# airswimmer-controller.net
KiCad netlist of a schematic drawn in EAGLE
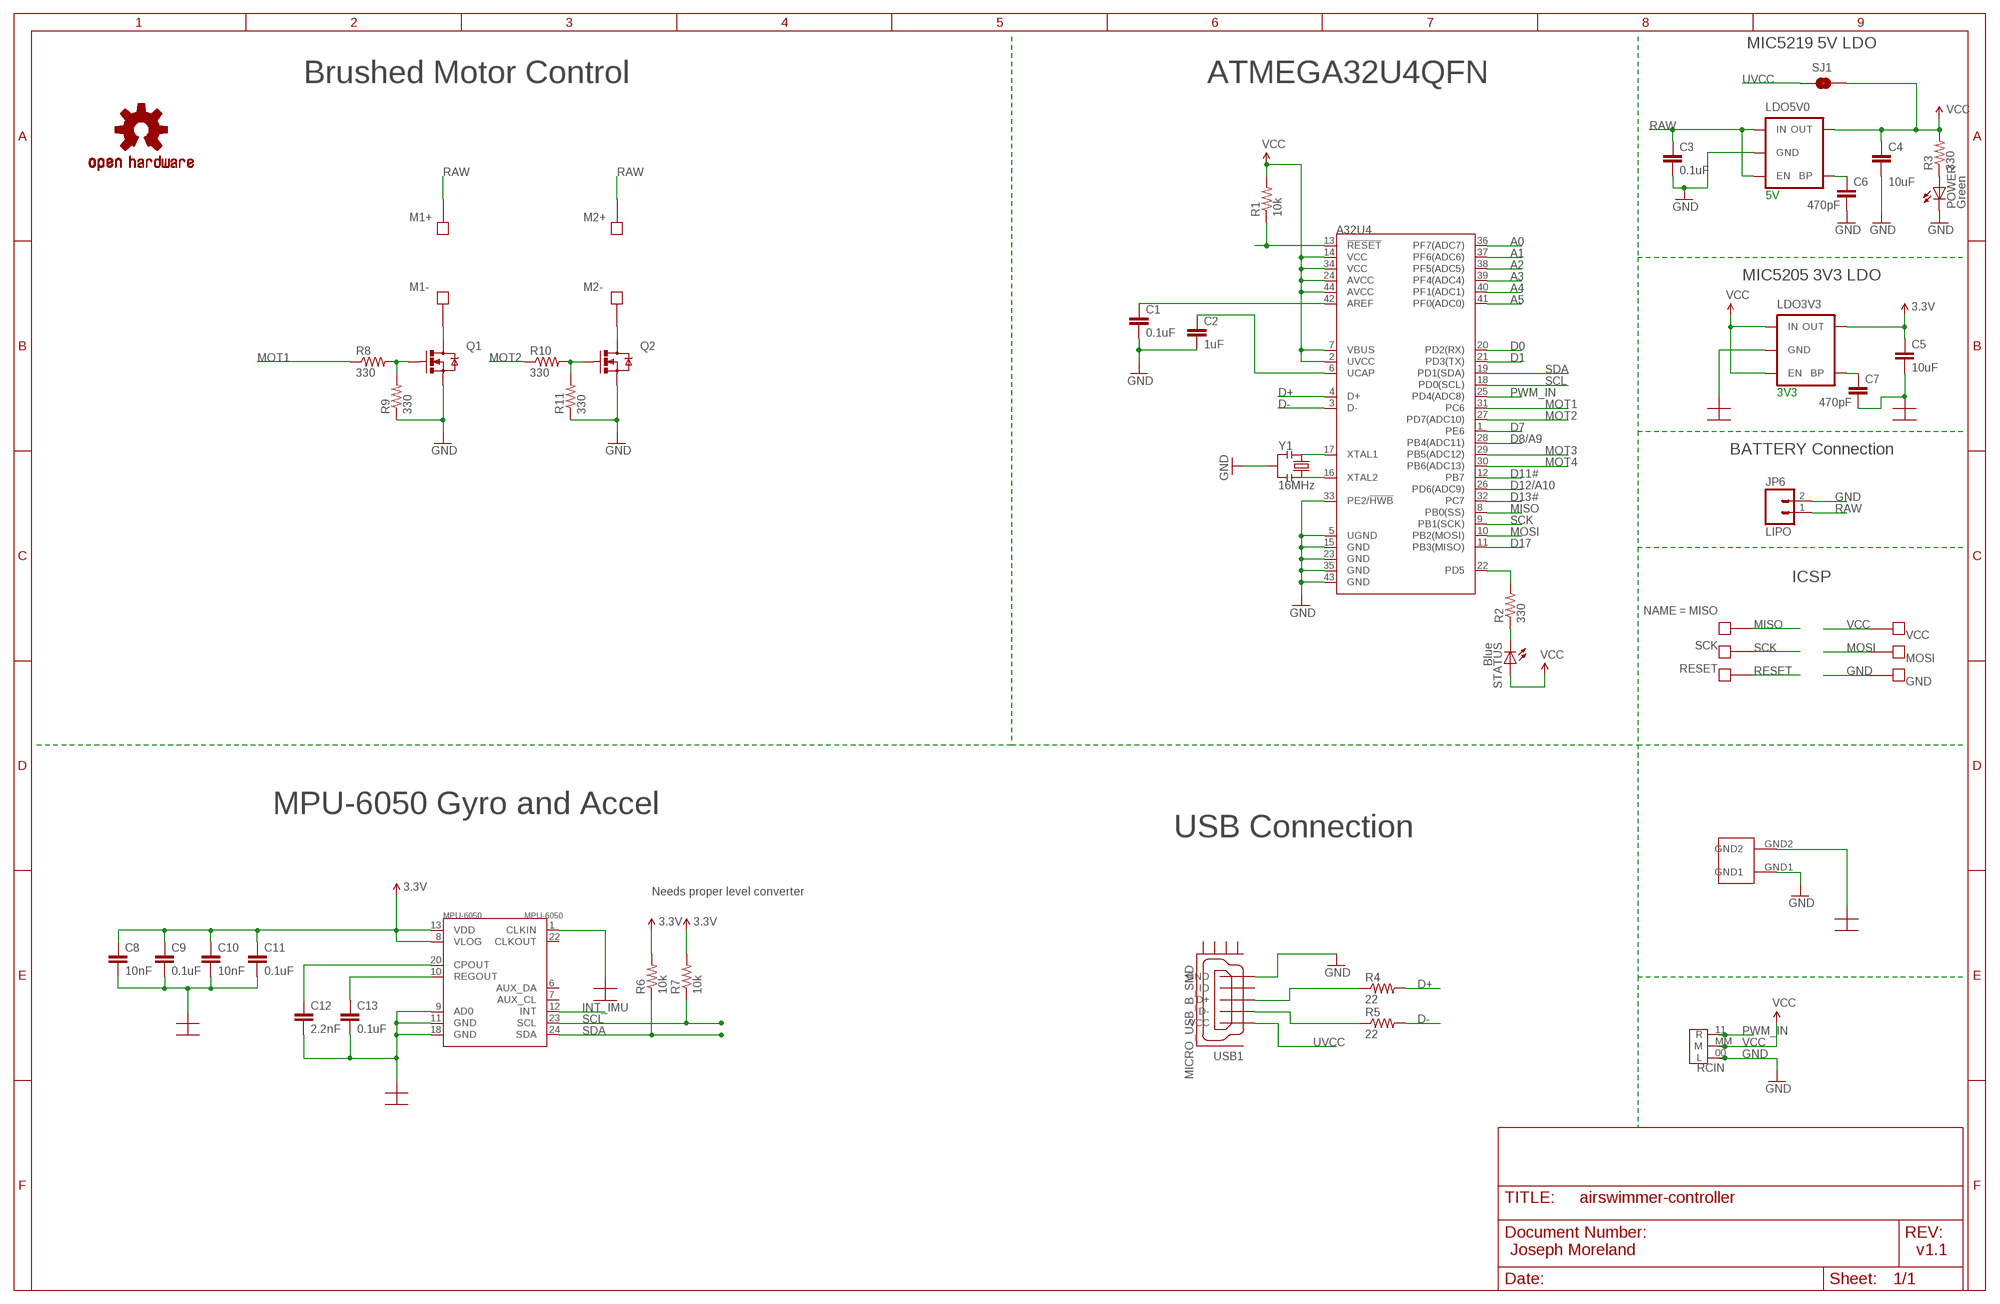
[diagram p0: schematic, sheet 1]

(export (version "E")
  (design (tool "Eeschema 10.0.6"))
  (components
    (comp (ref "A32U4")
      (value "ATMEGA32U4QFN")
      (footprint "eagle-import:ATMEL_QFN-44_SMALL_PAD")
      (fields (field (name "PARTNO") "ATMEGA32U4-MU"))
      (libsource (lib "eagle-import") (part "ATMEGA32U4QFN"))
    )
    (comp (ref "C1")
      (value "0.1uF")
      (footprint "eagle-import:SPARKFUN_0402-CAP")
      (fields (field (name "PARTNO") "GMK105BJ104KV-F"))
      (libsource (lib "eagle-import") (part "SPARKFUN_CAP0402-CAP"))
    )
    (comp (ref "C2")
      (value "1uF")
      (footprint "eagle-import:SPARKFUN_0402-CAP")
      (fields (field (name "PARTNO") "LMK105BJ105KV-F"))
      (libsource (lib "eagle-import") (part "SPARKFUN_CAP0402-CAP"))
    )
    (comp (ref "C3")
      (value "0.1uF")
      (footprint "eagle-import:SPARKFUN_0402-CAP")
      (fields (field (name "PARTNO") "GMK105BJ104KV-F"))
      (libsource (lib "eagle-import") (part "SPARKFUN_CAP0402-CAP"))
    )
    (comp (ref "C4")
      (value "10uF")
      (footprint "eagle-import:0603-CAP")
      (fields (field (name "PARTNO") "TCM1A106M8R"))
      (libsource (lib "eagle-import") (part "CAP0603-CAP"))
    )
    (comp (ref "C5")
      (value "10uF")
      (footprint "eagle-import:0603-CAP")
      (fields (field (name "PARTNO") "TCM1A106M8R"))
      (libsource (lib "eagle-import") (part "CAP0603-CAP"))
    )
    (comp (ref "C6")
      (value "470pF")
      (footprint "eagle-import:0603-CAP")
      (fields (field (name "PARTNO") "C0603C471K5RACTU"))
      (libsource (lib "eagle-import") (part "CAP0603-CAP"))
    )
    (comp (ref "C7")
      (value "470pF")
      (footprint "eagle-import:0603-CAP")
      (fields (field (name "PARTNO") "C0603C471K5RACTU"))
      (libsource (lib "eagle-import") (part "CAP0603-CAP"))
    )
    (comp (ref "C8")
      (value "10nF")
      (footprint "eagle-import:0402-CAP")
      (fields (field (name "PARTNO") "C0402C103K8RACTU"))
      (libsource (lib "eagle-import") (part "CAP0402-CAP"))
    )
    (comp (ref "C9")
      (value "0.1uF")
      (footprint "eagle-import:0402-CAP")
      (fields (field (name "PARTNO") "GMK105BJ104KV-F"))
      (libsource (lib "eagle-import") (part "CAP0402-CAP"))
    )
    (comp (ref "C10")
      (value "10nF")
      (footprint "eagle-import:0402-CAP")
      (fields (field (name "PARTNO") "C0402C103K8RACTU"))
      (libsource (lib "eagle-import") (part "CAP0402-CAP"))
    )
    (comp (ref "C11")
      (value "0.1uF")
      (footprint "eagle-import:0402-CAP")
      (fields (field (name "PARTNO") "GMK105BJ104KV-F"))
      (libsource (lib "eagle-import") (part "CAP0402-CAP"))
    )
    (comp (ref "C12")
      (value "2.2nF")
      (footprint "eagle-import:0402-CAP")
      (fields (field (name "PARTNO") "C0402C222K4RACTU"))
      (libsource (lib "eagle-import") (part "CAP0402-CAP"))
    )
    (comp (ref "C13")
      (value "0.1uF")
      (footprint "eagle-import:0402-CAP")
      (fields (field (name "PARTNO") "GMK105BJ104KV-F"))
      (libsource (lib "eagle-import") (part "CAP0402-CAP"))
    )
    (comp (ref "GND")
      (value "TEST_PAD")
      (footprint "eagle-import:ICSP_PAD")
      (fields (field (name "PARTNO") "DNP"))
      (libsource (lib "eagle-import") (part "TEST_PAD"))
    )
    (comp (ref "GND_SHORT")
      (value "GND_SHORT")
      (footprint "eagle-import:GND_SHORT")
      (fields (field (name "PARTNO") "DNP"))
      (libsource (lib "eagle-import") (part "GND_SHORT"))
    )
    (comp (ref "JP6")
      (value "LIPO")
      (footprint "eagle-import:1X02_LOCK")
      (fields (field (name "PARTNO") "DNP"))
      (libsource (lib "eagle-import") (part "M02LOCK"))
    )
    (comp (ref "LDO3V3")
      (value "V_REG_MIC52193.3V")
      (footprint "eagle-import:SOT23-5")
      (fields (field (name "PARTNO") "MIC5219-3.3YM5 TR"))
      (libsource (lib "eagle-import") (part "V_REG_MIC52193.3V"))
    )
    (comp (ref "LDO5V0")
      (value "MIC5219")
      (footprint "eagle-import:SOT23-5")
      (fields (field (name "PARTNO") "MIC5219-5.0YM5 TR"))
      (libsource (lib "eagle-import") (part "V_REG_MIC52195V"))
    )
    (comp (ref "LOGO1")
      (value "OSHW-LOGOM")
      (footprint "eagle-import:OSHW-LOGO-M")
      (fields (field (name "PARTNO") "DNP"))
      (libsource (lib "eagle-import") (part "OSHW-LOGOM"))
    )
    (comp (ref "M1+")
      (value "SOLDER_PAD.05X.05")
      (footprint "eagle-import:SOLDER_PAD_.05X.05")
      (fields (field (name "PARTNO") "DNP"))
      (libsource (lib "eagle-import") (part "SOLDER_PAD.05X.05"))
    )
    (comp (ref "M1-")
      (value "SOLDER_PAD.05X.05")
      (footprint "eagle-import:SOLDER_PAD_.05X.05")
      (fields (field (name "PARTNO") "DNP"))
      (libsource (lib "eagle-import") (part "SOLDER_PAD.05X.05"))
    )
    (comp (ref "M2+")
      (value "SOLDER_PAD.05X.05")
      (footprint "eagle-import:SOLDER_PAD_.05X.05")
      (fields (field (name "PARTNO") "DNP"))
      (libsource (lib "eagle-import") (part "SOLDER_PAD.05X.05"))
    )
    (comp (ref "M2-")
      (value "SOLDER_PAD.05X.05")
      (footprint "eagle-import:SOLDER_PAD_.05X.05")
      (fields (field (name "PARTNO") "DNP"))
      (libsource (lib "eagle-import") (part "SOLDER_PAD.05X.05"))
    )
    (comp (ref "MISO")
      (value "TEST_PAD")
      (footprint "eagle-import:ICSP_PAD")
      (fields (field (name "PARTNO") "DNP"))
      (libsource (lib "eagle-import") (part "TEST_PAD"))
    )
    (comp (ref "MOSI")
      (value "TEST_PAD")
      (footprint "eagle-import:ICSP_PAD")
      (fields (field (name "PARTNO") "DNP"))
      (libsource (lib "eagle-import") (part "TEST_PAD"))
    )
    (comp (ref "MPU-6050")
      (value "MPU-6050")
      (footprint "eagle-import:QFN-24")
      (libsource (lib "eagle-import") (part "IMU3000"))
    )
    (comp (ref "POWER")
      (value "Green")
      (footprint "eagle-import:LED-0603")
      (fields (field (name "PARTNO") "LTST-C190KGKT"))
      (libsource (lib "eagle-import") (part "LED0603"))
    )
    (comp (ref "Q1")
      (value "MOSFET-NCHANNELBSS123LT1G")
      (footprint "eagle-import:SOT23")
      (fields (field (name "PARTNO") "DMG6968U-7"))
      (libsource (lib "eagle-import") (part "MOSFET-NCHANNELBSS123LT1G"))
    )
    (comp (ref "Q2")
      (value "MOSFET-NCHANNELBSS123LT1G")
      (footprint "eagle-import:SOT23")
      (fields (field (name "PARTNO") "DMG6968U-7"))
      (libsource (lib "eagle-import") (part "MOSFET-NCHANNELBSS123LT1G"))
    )
    (comp (ref "R1")
      (value "10k")
      (footprint "eagle-import:0402-RES")
      (fields (field (name "PARTNO") "CRCW040210K0FKED"))
      (libsource (lib "eagle-import") (part "SparkFun-Resistors_RESISTOR0402-RES"))
    )
    (comp (ref "R2")
      (value "330")
      (footprint "eagle-import:0402-RES")
      (fields (field (name "PARTNO") "CRCW0402330RJNED"))
      (libsource (lib "eagle-import") (part "SparkFun-Resistors_RESISTOR0402-RES"))
    )
    (comp (ref "R3")
      (value "330")
      (footprint "eagle-import:0402-RES")
      (fields (field (name "PARTNO") "CRCW0402330RJNED"))
      (libsource (lib "eagle-import") (part "SparkFun-Resistors_RESISTOR0402-RES"))
    )
    (comp (ref "R4")
      (value "22")
      (footprint "eagle-import:0402-RES")
      (fields (field (name "PARTNO") "CRCW040222R0JNED"))
      (libsource (lib "eagle-import") (part "SparkFun-Resistors_RESISTOR0402-RES"))
    )
    (comp (ref "R5")
      (value "22")
      (footprint "eagle-import:0402-RES")
      (fields (field (name "PARTNO") "CRCW040222R0JNED"))
      (libsource (lib "eagle-import") (part "SparkFun-Resistors_RESISTOR0402-RES"))
    )
    (comp (ref "R6")
      (value "10k")
      (footprint "eagle-import:0402-RES")
      (fields (field (name "PARTNO") "CRCW040210K0FKED"))
      (libsource (lib "eagle-import") (part "RESISTOR0402-RES"))
    )
    (comp (ref "R7")
      (value "10k")
      (footprint "eagle-import:0402-RES")
      (fields (field (name "PARTNO") "CRCW040210K0FKED"))
      (libsource (lib "eagle-import") (part "RESISTOR0402-RES"))
    )
    (comp (ref "R8")
      (value "330")
      (footprint "eagle-import:0402-RES")
      (fields (field (name "PARTNO") "CRCW0402330RJNED"))
      (libsource (lib "eagle-import") (part "RESISTOR0402-RES"))
    )
    (comp (ref "R9")
      (value "330")
      (footprint "eagle-import:0402-RES")
      (fields (field (name "PARTNO") "CRCW0402330RJNED"))
      (libsource (lib "eagle-import") (part "RESISTOR0402-RES"))
    )
    (comp (ref "R10")
      (value "330")
      (footprint "eagle-import:0402-RES")
      (fields (field (name "PARTNO") "CRCW0402330RJNED"))
      (libsource (lib "eagle-import") (part "RESISTOR0402-RES"))
    )
    (comp (ref "R11")
      (value "330")
      (footprint "eagle-import:0402-RES")
      (fields (field (name "PARTNO") "CRCW0402330RJNED"))
      (libsource (lib "eagle-import") (part "RESISTOR0402-RES"))
    )
    (comp (ref "RCIN")
      (value "PAD-JUMPER-3P40*40")
      (footprint "eagle-import:3P-SMD-4.1X1.5")
      (fields (field (name "PARTNO") "DNP"))
      (libsource (lib "eagle-import") (part "PAD-JUMPER-3P4040"))
    )
    (comp (ref "RESET")
      (value "TEST_PAD")
      (footprint "eagle-import:ICSP_PAD")
      (fields (field (name "PARTNO") "DNP"))
      (libsource (lib "eagle-import") (part "TEST_PAD"))
    )
    (comp (ref "SCK")
      (value "TEST_PAD")
      (footprint "eagle-import:ICSP_PAD")
      (fields (field (name "PARTNO") "DNP"))
      (libsource (lib "eagle-import") (part "TEST_PAD"))
    )
    (comp (ref "SJ1")
      (value "P-USB")
      (footprint "eagle-import:SPARKFUN_SJ_2S")
      (fields (field (name "PARTNO") "DNP"))
      (libsource (lib "eagle-import") (part "SPARKFUN_SOLDERJUMPERNC"))
    )
    (comp (ref "STATUS")
      (value "Blue")
      (footprint "eagle-import:LED-0603")
      (fields (field (name "PARTNO") "LTST-C191TBKT"))
      (libsource (lib "eagle-import") (part "LED0603"))
    )
    (comp (ref "USB1")
      (value "MICRO_USB_B_SMD")
      (footprint "eagle-import:MOLEX_MICRO_USB_B_BOTTOM_MOUNT")
      (fields (field (name "PARTNO") "473460001"))
      (libsource (lib "eagle-import") (part "MICRO_USB_B_SMD"))
    )
    (comp (ref "VCC")
      (value "TEST_PAD")
      (footprint "eagle-import:ICSP_PAD")
      (fields (field (name "PARTNO") "DNP"))
      (libsource (lib "eagle-import") (part "TEST_PAD"))
    )
    (comp (ref "Y1")
      (value "16MHz")
      (footprint "eagle-import:RESONATOR-SMD")
      (fields (field (name "PARTNO") "CSTCE16M0V53-R0"))
      (libsource (lib "eagle-import") (part "RESONATOR16MHZ"))
    )
  )
  (nets
    (net (code "1") (name "/A0") (class "Default")
      (node (ref "A32U4") (pin "36") (pinfunction "PF7(ADC7)_36") (pintype "bidirectional"))
    )
    (net (code "2") (name "/A1") (class "Default")
      (node (ref "A32U4") (pin "37") (pinfunction "PF6(ADC6)_37") (pintype "bidirectional"))
    )
    (net (code "3") (name "/A2") (class "Default")
      (node (ref "A32U4") (pin "38") (pinfunction "PF5(ADC5)_38") (pintype "bidirectional"))
    )
    (net (code "4") (name "/A3") (class "Default")
      (node (ref "A32U4") (pin "39") (pinfunction "PF4(ADC4)_39") (pintype "bidirectional"))
    )
    (net (code "5") (name "/A4") (class "Default")
      (node (ref "A32U4") (pin "40") (pinfunction "PF1(ADC1)_40") (pintype "bidirectional"))
    )
    (net (code "6") (name "/A5") (class "Default")
      (node (ref "A32U4") (pin "41") (pinfunction "PF0(ADC0)_41") (pintype "bidirectional"))
    )
    (net (code "7") (name "/D+") (class "Default")
      (node (ref "A32U4") (pin "4") (pinfunction "D+_4") (pintype "bidirectional"))
      (node (ref "R4") (pin "2") (pinfunction "2_2") (pintype "passive"))
    )
    (net (code "8") (name "/D-") (class "Default")
      (node (ref "A32U4") (pin "3") (pinfunction "D-_3") (pintype "bidirectional"))
      (node (ref "R5") (pin "2") (pinfunction "2_2") (pintype "passive"))
    )
    (net (code "9") (name "/D0") (class "Default")
      (node (ref "A32U4") (pin "20") (pinfunction "PD2(RX)_20") (pintype "bidirectional"))
    )
    (net (code "10") (name "/D1") (class "Default")
      (node (ref "A32U4") (pin "21") (pinfunction "PD3(TX)_21") (pintype "bidirectional"))
    )
    (net (code "11") (name "/D7") (class "Default")
      (node (ref "A32U4") (pin "1") (pinfunction "PE6_1") (pintype "bidirectional"))
    )
    (net (code "12") (name "/D8{slash}A9") (class "Default")
      (node (ref "A32U4") (pin "28") (pinfunction "PB4(ADC11)_28") (pintype "bidirectional"))
    )
    (net (code "13") (name "/D11#") (class "Default")
      (node (ref "A32U4") (pin "12") (pinfunction "PB7_12") (pintype "bidirectional"))
    )
    (net (code "14") (name "/D12{slash}A10") (class "Default")
      (node (ref "A32U4") (pin "26") (pinfunction "PD6(ADC9)_26") (pintype "bidirectional"))
    )
    (net (code "15") (name "/D13#") (class "Default")
      (node (ref "A32U4") (pin "32") (pinfunction "PC7_32") (pintype "bidirectional"))
    )
    (net (code "16") (name "/D17") (class "Default")
      (node (ref "A32U4") (pin "11") (pinfunction "PB3(MISO)_11") (pintype "bidirectional"))
    )
    (net (code "17") (name "/INT_IMU") (class "Default")
      (node (ref "MPU-6050") (pin "12") (pinfunction "INT_12") (pintype "bidirectional"))
    )
    (net (code "18") (name "/MISO") (class "Default")
      (node (ref "A32U4") (pin "8") (pinfunction "PB0(SS)_8") (pintype "bidirectional"))
      (node (ref "MISO") (pin "P$1") (pinfunction "NET_P$1") (pintype "bidirectional"))
    )
    (net (code "19") (name "/MOSI") (class "Default")
      (node (ref "A32U4") (pin "10") (pinfunction "PB2(MOSI)_10") (pintype "bidirectional"))
      (node (ref "MOSI") (pin "P$1") (pinfunction "NET_P$1") (pintype "bidirectional"))
    )
    (net (code "20") (name "/MOT1") (class "Default")
      (node (ref "A32U4") (pin "31") (pinfunction "PC6_31") (pintype "bidirectional"))
      (node (ref "R8") (pin "1") (pinfunction "1_1") (pintype "passive"))
    )
    (net (code "21") (name "/MOT2") (class "Default")
      (node (ref "A32U4") (pin "27") (pinfunction "PD7(ADC10)_27") (pintype "bidirectional"))
      (node (ref "R10") (pin "1") (pinfunction "1_1") (pintype "passive"))
    )
    (net (code "22") (name "/MOT3") (class "Default")
      (node (ref "A32U4") (pin "29") (pinfunction "PB5(ADC12)_29") (pintype "bidirectional"))
    )
    (net (code "23") (name "/MOT4") (class "Default")
      (node (ref "A32U4") (pin "30") (pinfunction "PB6(ADC13)_30") (pintype "bidirectional"))
    )
    (net (code "24") (name "/PWM_IN") (class "Default")
      (node (ref "A32U4") (pin "25") (pinfunction "PD4(ADC8)_25") (pintype "bidirectional"))
      (node (ref "RCIN") (pin "11") (pinfunction "R_11") (pintype "bidirectional"))
    )
    (net (code "25") (name "/RAW") (class "Default")
      (node (ref "C3") (pin "1") (pinfunction "1_1") (pintype "passive"))
      (node (ref "JP6") (pin "1") (pinfunction "1_1") (pintype "passive"))
      (node (ref "LDO5V0") (pin "1") (pinfunction "IN_1") (pintype "input"))
      (node (ref "LDO5V0") (pin "3") (pinfunction "EN_3") (pintype "input"))
      (node (ref "M1+") (pin "P$1") (pinfunction "NET_P$1") (pintype "bidirectional"))
      (node (ref "M2+") (pin "P$1") (pinfunction "NET_P$1") (pintype "bidirectional"))
    )
    (net (code "26") (name "/RESET") (class "Default")
      (node (ref "A32U4") (pin "13") (pinfunction "~{RESET}_13") (pintype "bidirectional"))
      (node (ref "R1") (pin "1") (pinfunction "1_1") (pintype "passive"))
      (node (ref "RESET") (pin "P$1") (pinfunction "NET_P$1") (pintype "bidirectional"))
    )
    (net (code "27") (name "/SCK") (class "Default")
      (node (ref "A32U4") (pin "9") (pinfunction "PB1(SCK)_9") (pintype "bidirectional"))
      (node (ref "SCK") (pin "P$1") (pinfunction "NET_P$1") (pintype "bidirectional"))
    )
    (net (code "28") (name "/SCL") (class "Default")
      (node (ref "A32U4") (pin "18") (pinfunction "PD0(SCL)_18") (pintype "bidirectional"))
      (node (ref "MPU-6050") (pin "23") (pinfunction "SCL_23") (pintype "bidirectional"))
      (node (ref "R7") (pin "1") (pinfunction "1_1") (pintype "passive"))
    )
    (net (code "29") (name "/SDA") (class "Default")
      (node (ref "A32U4") (pin "19") (pinfunction "PD1(SDA)_19") (pintype "bidirectional"))
      (node (ref "MPU-6050") (pin "24") (pinfunction "SDA_24") (pintype "bidirectional"))
      (node (ref "R6") (pin "1") (pinfunction "1_1") (pintype "passive"))
    )
    (net (code "30") (name "/UVCC") (class "Default")
      (node (ref "SJ1") (pin "1") (pinfunction "1_1") (pintype "passive"))
      (node (ref "USB1") (pin "1") (pinfunction "VCC_1") (pintype "input"))
    )
    (net (code "31") (name "3.3V") (class "Default")
      (node (ref "C10") (pin "1") (pinfunction "1_1") (pintype "passive"))
      (node (ref "C11") (pin "1") (pinfunction "1_1") (pintype "passive"))
      (node (ref "C5") (pin "1") (pinfunction "1_1") (pintype "passive"))
      (node (ref "C8") (pin "1") (pinfunction "1_1") (pintype "passive"))
      (node (ref "C9") (pin "1") (pinfunction "1_1") (pintype "passive"))
      (node (ref "LDO3V3") (pin "5") (pinfunction "OUT_5") (pintype "passive"))
      (node (ref "MPU-6050") (pin "13") (pinfunction "VDD_13") (pintype "bidirectional"))
      (node (ref "MPU-6050") (pin "8") (pinfunction "VLOG_8") (pintype "bidirectional"))
      (node (ref "R6") (pin "2") (pinfunction "2_2") (pintype "passive"))
      (node (ref "R7") (pin "2") (pinfunction "2_2") (pintype "passive"))
    )
    (net (code "32") (name "DGND") (class "Default")
      (node (ref "C10") (pin "2") (pinfunction "2_2") (pintype "passive"))
      (node (ref "C11") (pin "2") (pinfunction "2_2") (pintype "passive"))
      (node (ref "C12") (pin "2") (pinfunction "2_2") (pintype "passive"))
      (node (ref "C13") (pin "2") (pinfunction "2_2") (pintype "passive"))
      (node (ref "C5") (pin "2") (pinfunction "2_2") (pintype "passive"))
      (node (ref "C7") (pin "2") (pinfunction "2_2") (pintype "passive"))
      (node (ref "C8") (pin "2") (pinfunction "2_2") (pintype "passive"))
      (node (ref "C9") (pin "2") (pinfunction "2_2") (pintype "passive"))
      (node (ref "GND_SHORT") (pin "GND2") (pinfunction "GND2_GND2") (pintype "power_in"))
      (node (ref "LDO3V3") (pin "2") (pinfunction "GND_2") (pintype "input"))
      (node (ref "MPU-6050") (pin "1") (pinfunction "CLKIN_1") (pintype "bidirectional"))
      (node (ref "MPU-6050") (pin "11") (pinfunction "GND_11") (pintype "bidirectional"))
      (node (ref "MPU-6050") (pin "18") (pinfunction "GND_18") (pintype "bidirectional"))
      (node (ref "MPU-6050") (pin "9") (pinfunction "AD0_9") (pintype "bidirectional"))
    )
    (net (code "33") (name "GND") (class "Default")
      (node (ref "A32U4") (pin "15") (pinfunction "GND_15") (pintype "bidirectional"))
      (node (ref "A32U4") (pin "23") (pinfunction "GND_23") (pintype "bidirectional"))
      (node (ref "A32U4") (pin "33") (pinfunction "PE2/~{HWB}_33") (pintype "bidirectional"))
      (node (ref "A32U4") (pin "35") (pinfunction "GND_35") (pintype "bidirectional"))
      (node (ref "A32U4") (pin "43") (pinfunction "GND_43") (pintype "bidirectional"))
      (node (ref "A32U4") (pin "5") (pinfunction "UGND_5") (pintype "bidirectional"))
      (node (ref "C1") (pin "2") (pinfunction "2_2") (pintype "passive"))
      (node (ref "C2") (pin "2") (pinfunction "2_2") (pintype "passive"))
      (node (ref "C3") (pin "2") (pinfunction "2_2") (pintype "passive"))
      (node (ref "C4") (pin "2") (pinfunction "2_2") (pintype "passive"))
      (node (ref "C6") (pin "2") (pinfunction "2_2") (pintype "passive"))
      (node (ref "GND") (pin "P$1") (pinfunction "NET_P$1") (pintype "bidirectional"))
      (node (ref "GND_SHORT") (pin "GND1") (pinfunction "GND1_GND1") (pintype "power_in"))
      (node (ref "JP6") (pin "2") (pinfunction "2_2") (pintype "passive"))
      (node (ref "LDO5V0") (pin "2") (pinfunction "GND_2") (pintype "input"))
      (node (ref "POWER") (pin "C") (pinfunction "C_C") (pintype "passive"))
      (node (ref "Q1") (pin "2") (pinfunction "S_2") (pintype "passive"))
      (node (ref "Q2") (pin "2") (pinfunction "S_2") (pintype "passive"))
      (node (ref "R11") (pin "1") (pinfunction "1_1") (pintype "passive"))
      (node (ref "R9") (pin "1") (pinfunction "1_1") (pintype "passive"))
      (node (ref "RCIN") (pin "00") (pinfunction "L_00") (pintype "bidirectional"))
      (node (ref "USB1") (pin "5") (pinfunction "GND_5") (pintype "input"))
      (node (ref "Y1") (pin "2") (pinfunction "2_2") (pintype "passive"))
    )
    (net (code "34") (name "Net-(A32U4-AREF)") (class "Default")
      (node (ref "A32U4") (pin "42") (pinfunction "AREF_42") (pintype "bidirectional"))
      (node (ref "C1") (pin "1") (pinfunction "1_1") (pintype "passive"))
    )
    (net (code "35") (name "Net-(A32U4-PD5)") (class "Default")
      (node (ref "A32U4") (pin "22") (pinfunction "PD5_22") (pintype "bidirectional"))
      (node (ref "R2") (pin "2") (pinfunction "2_2") (pintype "passive"))
    )
    (net (code "36") (name "Net-(A32U4-UCAP)") (class "Default")
      (node (ref "A32U4") (pin "6") (pinfunction "UCAP_6") (pintype "bidirectional"))
      (node (ref "C2") (pin "1") (pinfunction "1_1") (pintype "passive"))
    )
    (net (code "37") (name "Net-(A32U4-XTAL1)") (class "Default")
      (node (ref "A32U4") (pin "17") (pinfunction "XTAL1_17") (pintype "bidirectional"))
      (node (ref "Y1") (pin "1") (pinfunction "1_1") (pintype "passive"))
    )
    (net (code "38") (name "Net-(A32U4-XTAL2)") (class "Default")
      (node (ref "A32U4") (pin "16") (pinfunction "XTAL2_16") (pintype "bidirectional"))
      (node (ref "Y1") (pin "3") (pinfunction "3_3") (pintype "passive"))
    )
    (net (code "39") (name "Net-(LDO3V3-BP)") (class "Default")
      (node (ref "C7") (pin "1") (pinfunction "1_1") (pintype "passive"))
      (node (ref "LDO3V3") (pin "4") (pinfunction "BP_4") (pintype "input"))
    )
    (net (code "40") (name "Net-(LDO5V0-BP)") (class "Default")
      (node (ref "C6") (pin "1") (pinfunction "1_1") (pintype "passive"))
      (node (ref "LDO5V0") (pin "4") (pinfunction "BP_4") (pintype "input"))
    )
    (net (code "41") (name "Net-(M1--NET)") (class "Default")
      (node (ref "M1-") (pin "P$1") (pinfunction "NET_P$1") (pintype "bidirectional"))
      (node (ref "Q1") (pin "3") (pinfunction "D_3") (pintype "passive"))
    )
    (net (code "42") (name "Net-(M2--NET)") (class "Default")
      (node (ref "M2-") (pin "P$1") (pinfunction "NET_P$1") (pintype "bidirectional"))
      (node (ref "Q2") (pin "3") (pinfunction "D_3") (pintype "passive"))
    )
    (net (code "43") (name "Net-(MPU-6050-CPOUT)") (class "Default")
      (node (ref "C12") (pin "1") (pinfunction "1_1") (pintype "passive"))
      (node (ref "MPU-6050") (pin "20") (pinfunction "CPOUT_20") (pintype "bidirectional"))
    )
    (net (code "44") (name "Net-(MPU-6050-REGOUT)") (class "Default")
      (node (ref "C13") (pin "1") (pinfunction "1_1") (pintype "passive"))
      (node (ref "MPU-6050") (pin "10") (pinfunction "REGOUT_10") (pintype "bidirectional"))
    )
    (net (code "45") (name "Net-(POWER-PadA)") (class "Default")
      (node (ref "POWER") (pin "A") (pinfunction "A_A") (pintype "passive"))
      (node (ref "R3") (pin "1") (pinfunction "1_1") (pintype "passive"))
    )
    (net (code "46") (name "Net-(Q1-G)") (class "Default")
      (node (ref "Q1") (pin "1") (pinfunction "G_1") (pintype "passive"))
      (node (ref "R8") (pin "2") (pinfunction "2_2") (pintype "passive"))
      (node (ref "R9") (pin "2") (pinfunction "2_2") (pintype "passive"))
    )
    (net (code "47") (name "Net-(Q2-G)") (class "Default")
      (node (ref "Q2") (pin "1") (pinfunction "G_1") (pintype "passive"))
      (node (ref "R10") (pin "2") (pinfunction "2_2") (pintype "passive"))
      (node (ref "R11") (pin "2") (pinfunction "2_2") (pintype "passive"))
    )
    (net (code "48") (name "Net-(R2-Pad1)") (class "Default")
      (node (ref "R2") (pin "1") (pinfunction "1_1") (pintype "passive"))
      (node (ref "STATUS") (pin "C") (pinfunction "C_C") (pintype "passive"))
    )
    (net (code "49") (name "Net-(USB1-D+)") (class "Default")
      (node (ref "R4") (pin "1") (pinfunction "1_1") (pintype "passive"))
      (node (ref "USB1") (pin "3") (pinfunction "D+_3") (pintype "input"))
    )
    (net (code "50") (name "Net-(USB1-D-)") (class "Default")
      (node (ref "R5") (pin "1") (pinfunction "1_1") (pintype "passive"))
      (node (ref "USB1") (pin "2") (pinfunction "D-_2") (pintype "input"))
    )
    (net (code "51") (name "VCC") (class "Default")
      (node (ref "A32U4") (pin "14") (pinfunction "VCC_14") (pintype "bidirectional"))
      (node (ref "A32U4") (pin "2") (pinfunction "UVCC_2") (pintype "bidirectional"))
      (node (ref "A32U4") (pin "24") (pinfunction "AVCC_24") (pintype "bidirectional"))
      (node (ref "A32U4") (pin "34") (pinfunction "VCC_34") (pintype "bidirectional"))
      (node (ref "A32U4") (pin "44") (pinfunction "AVCC_44") (pintype "bidirectional"))
      (node (ref "A32U4") (pin "7") (pinfunction "VBUS_7") (pintype "bidirectional"))
      (node (ref "C4") (pin "1") (pinfunction "1_1") (pintype "passive"))
      (node (ref "LDO3V3") (pin "1") (pinfunction "IN_1") (pintype "input"))
      (node (ref "LDO3V3") (pin "3") (pinfunction "EN_3") (pintype "input"))
      (node (ref "LDO5V0") (pin "5") (pinfunction "OUT_5") (pintype "passive"))
      (node (ref "R1") (pin "2") (pinfunction "2_2") (pintype "passive"))
      (node (ref "R3") (pin "2") (pinfunction "2_2") (pintype "passive"))
      (node (ref "RCIN") (pin "MM") (pinfunction "M_MM") (pintype "bidirectional"))
      (node (ref "SJ1") (pin "2") (pinfunction "2_2") (pintype "passive"))
      (node (ref "STATUS") (pin "A") (pinfunction "A_A") (pintype "passive"))
      (node (ref "VCC") (pin "P$1") (pinfunction "NET_P$1") (pintype "bidirectional"))
    )
    (net (code "52") (name "unconnected-(MPU-6050-AUX_CL-Pad7)") (class "Default")
      (node (ref "MPU-6050") (pin "7") (pinfunction "AUX_CL_7") (pintype "bidirectional"))
    )
    (net (code "53") (name "unconnected-(MPU-6050-AUX_DA-Pad6)") (class "Default")
      (node (ref "MPU-6050") (pin "6") (pinfunction "AUX_DA_6") (pintype "bidirectional"))
    )
    (net (code "54") (name "unconnected-(MPU-6050-CLKOUT-Pad22)") (class "Default")
      (node (ref "MPU-6050") (pin "22") (pinfunction "CLKOUT_22") (pintype "bidirectional"))
    )
    (net (code "55") (name "unconnected-(USB1-ID-Pad4)") (class "Default")
      (node (ref "USB1") (pin "4") (pinfunction "ID_4") (pintype "input"))
    )
    (net (code "56") (name "unconnected-(USB1-PadGND1)") (class "Default")
      (node (ref "USB1") (pin "GND1") (pinfunction "GND1_GND1") (pintype "bidirectional"))
    )
    (net (code "57") (name "unconnected-(USB1-PadGND2)") (class "Default")
      (node (ref "USB1") (pin "GND2") (pinfunction "GND2_GND2") (pintype "bidirectional"))
    )
    (net (code "58") (name "unconnected-(USB1-PadGND3)") (class "Default")
      (node (ref "USB1") (pin "GND3") (pinfunction "GND3_GND3") (pintype "bidirectional"))
    )
    (net (code "59") (name "unconnected-(USB1-PadGND4)") (class "Default")
      (node (ref "USB1") (pin "GND4") (pinfunction "GND4_GND4") (pintype "bidirectional"))
    )
  )
)
